# XboxSerialAdapter.net
KiCad netlist of a schematic drawn in EAGLE
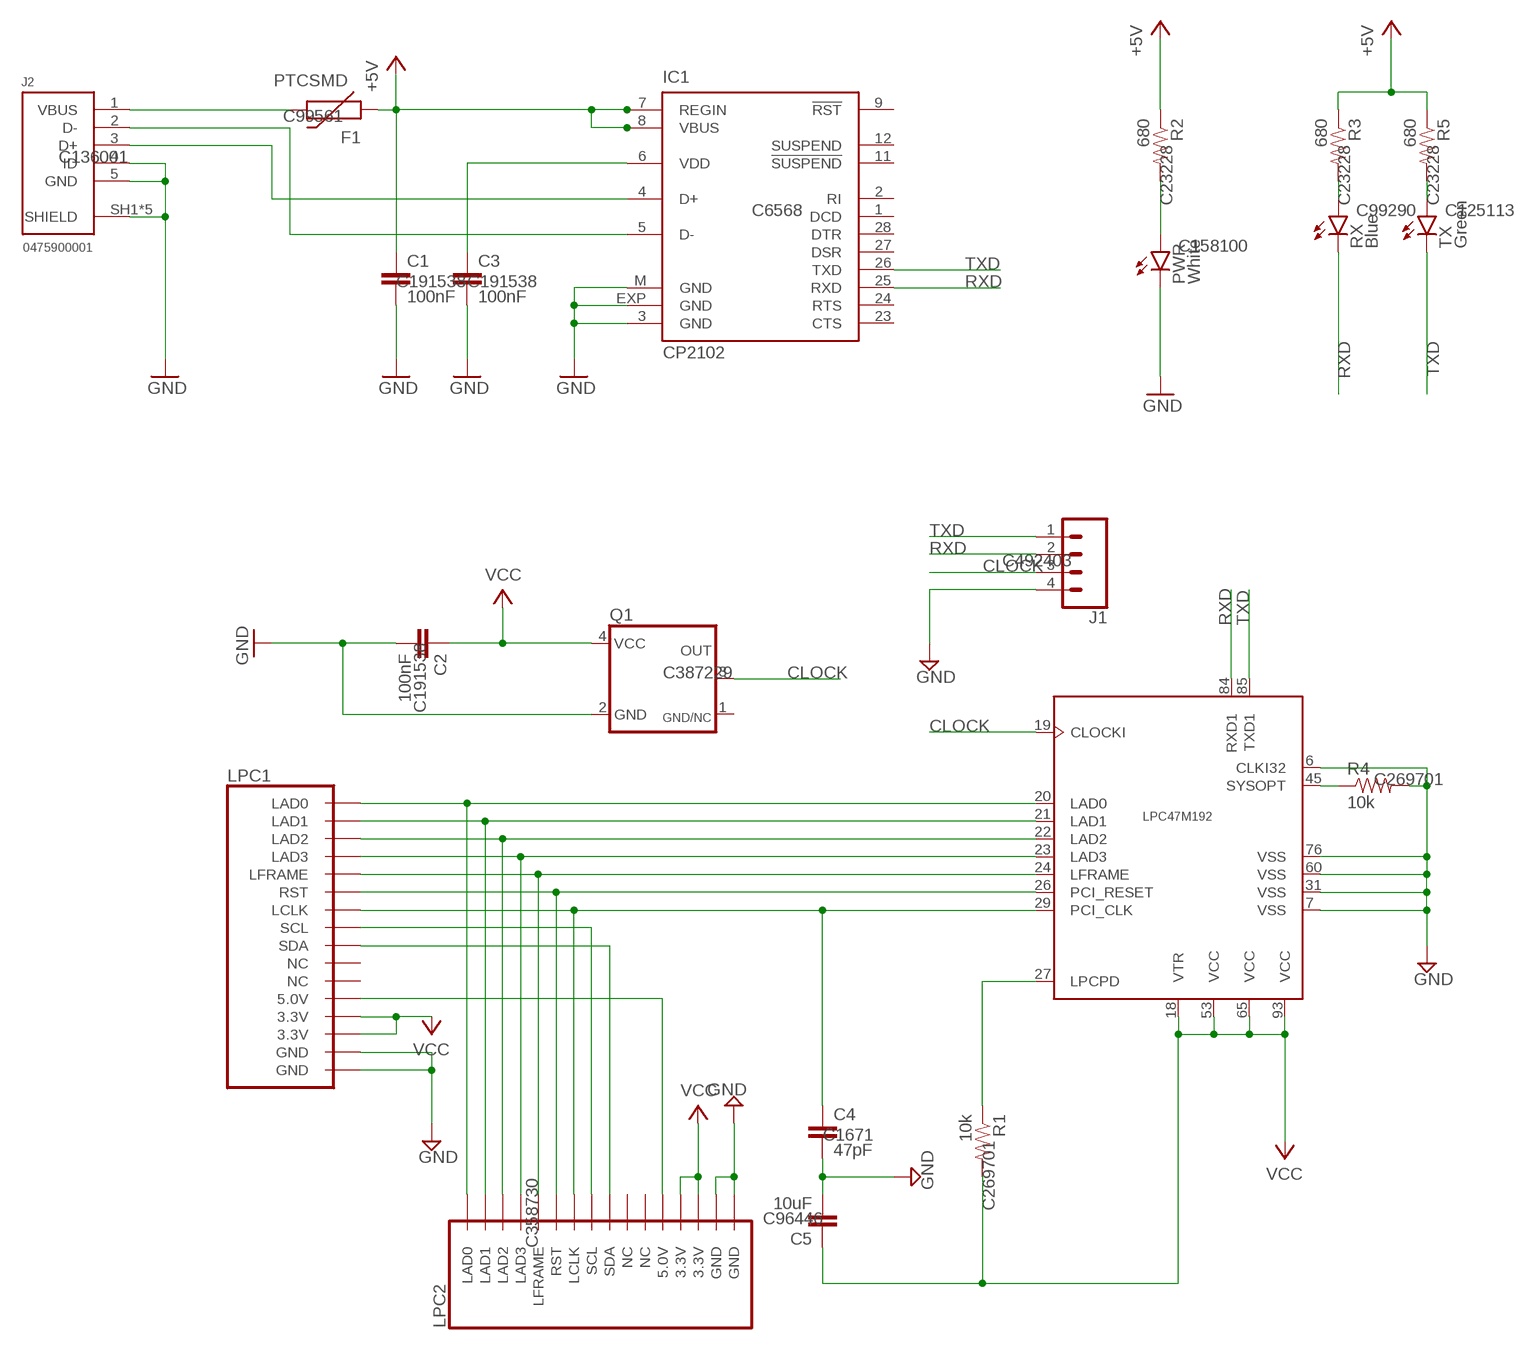
[diagram p0: schematic, sheet 1]

(export (version "E")
  (design (tool "Eeschema 10.0.6"))
  (components
    (comp (ref "C1")
      (value "100nF")
      (footprint "eagle-import:0603-CAP")
      (fields (field (name "LCSC_PART") "C191538"))
      (libsource (lib "eagle-import") (part "CAP0603-CAP"))
    )
    (comp (ref "C2")
      (value "100nF")
      (footprint "eagle-import:0603-CAP")
      (fields (field (name "LCSC_PART") "C191538"))
      (libsource (lib "eagle-import") (part "CAP0603-CAP"))
    )
    (comp (ref "C3")
      (value "100nF")
      (footprint "eagle-import:0603-CAP")
      (fields (field (name "LCSC_PART") "C191538"))
      (libsource (lib "eagle-import") (part "CAP0603-CAP"))
    )
    (comp (ref "C4")
      (value "47pF")
      (footprint "eagle-import:0603-CAP")
      (fields (field (name "LCSC_PART") "C1671"))
      (libsource (lib "eagle-import") (part "CAP0603-CAP"))
    )
    (comp (ref "C5")
      (value "10uF")
      (footprint "eagle-import:0603-CAP")
      (fields (field (name "LCSC_PART") "C96446"))
      (libsource (lib "eagle-import") (part "CAP0603-CAP"))
    )
    (comp (ref "F1")
      (value "PTCSMD")
      (footprint "eagle-import:PTC-1206")
      (fields (field (name "LCSC_PART") "C99561"))
      (libsource (lib "eagle-import") (part "PTCSMD"))
    )
    (comp (ref "IC1")
      (value "CP2102")
      (footprint "eagle-import:MLP28")
      (fields
        (field (name "MF") "FARNELL")
        (field (name "MPN") "CP2102-GM")
        (field (name "LCSC_PART") "C6568")
      )
      (libsource (lib "eagle-import") (part "CP2102"))
    )
    (comp (ref "J1")
      (value "CONN_04")
      (footprint "eagle-import:1X04")
      (fields (field (name "LCSC_PART") "C492403"))
      (libsource (lib "eagle-import") (part "CONN_04"))
    )
    (comp (ref "J2")
      (value "0475900001")
      (footprint "eagle-import:0475900001")
      (fields
        (field (name "DIGIKEY_PARTNO") "WM17144TR-ND")
        (field (name "MANUFACTURER") "Molex")
        (field (name "LCSC_PART") "C136001")
        (field (name "CREATED_BY") "PCBLayout.com")
      )
      (libsource (lib "eagle-import") (part "0475900001"))
    )
    (comp (ref "LPC1")
      (value "LPC_HEADERLPC_FEMALE")
      (footprint "eagle-import:HDRVR16W64P254_2X8_1524X508X254B")
      (fields (field (name "LCSC_PART") "C492425"))
      (libsource (lib "eagle-import") (part "LPC_HEADERLPC_FEMALE"))
    )
    (comp (ref "LPC2")
      (value "LPC_HEADERLPC_FEMALE")
      (footprint "eagle-import:HDRVR16W64P254_2X8_1524X508X254B")
      (fields (field (name "LCSC_PART") "C358730"))
      (libsource (lib "eagle-import") (part "LPC_HEADERLPC_FEMALE"))
    )
    (comp (ref "PWR")
      (value "White")
      (footprint "eagle-import:CHIP-LED0603")
      (fields (field (name "LCSC_PART") "C158100"))
      (libsource (lib "eagle-import") (part "LEDCHIP-LED0603"))
    )
    (comp (ref "Q1")
      (value "SCTF_C3872291")
      (footprint "eagle-import:SCTF_C387229")
      (fields (field (name "LCSC_PART") "C387229"))
      (libsource (lib "eagle-import") (part "SCTF_C3872291"))
    )
    (comp (ref "R1")
      (value "10k")
      (footprint "eagle-import:0603-RES")
      (fields (field (name "LCSC_PART") "C269701"))
      (libsource (lib "eagle-import") (part "RESISTOR0603-RES"))
    )
    (comp (ref "R2")
      (value "680")
      (footprint "eagle-import:0603-RES")
      (fields (field (name "LCSC_PART") "C23228"))
      (libsource (lib "eagle-import") (part "RESISTOR0603-RES"))
    )
    (comp (ref "R3")
      (value "680")
      (footprint "eagle-import:0603-RES")
      (fields (field (name "LCSC_PART") "C23228"))
      (libsource (lib "eagle-import") (part "RESISTOR0603-RES"))
    )
    (comp (ref "R4")
      (value "10k")
      (footprint "eagle-import:0603-RES")
      (fields (field (name "LCSC_PART") "C269701"))
      (libsource (lib "eagle-import") (part "RESISTOR0603-RES"))
    )
    (comp (ref "R5")
      (value "680")
      (footprint "eagle-import:0603-RES")
      (fields (field (name "LCSC_PART") "C23228"))
      (libsource (lib "eagle-import") (part "RESISTOR0603-RES"))
    )
    (comp (ref "RX")
      (value "Blue")
      (footprint "eagle-import:CHIP-LED0603")
      (fields (field (name "LCSC_PART") "C99290"))
      (libsource (lib "eagle-import") (part "LEDCHIP-LED0603"))
    )
    (comp (ref "TX")
      (value "Green")
      (footprint "eagle-import:CHIP-LED0603")
      (fields (field (name "LCSC_PART") "C125113"))
      (libsource (lib "eagle-import") (part "LEDCHIP-LED0603"))
    )
    (comp (ref "U1")
      (value "LPC47M192")
      (footprint "eagle-import:QFP128")
      (libsource (lib "eagle-import") (part "LPC47M192"))
    )
  )
  (nets
    (net (code "1") (name "+5V") (class "Default")
      (node (ref "C1") (pin "1") (pinfunction "1_1") (pintype "passive"))
      (node (ref "F1") (pin "1") (pinfunction "1_1") (pintype "bidirectional"))
      (node (ref "IC1") (pin "7") (pinfunction "REGIN_7") (pintype "passive"))
      (node (ref "IC1") (pin "8") (pinfunction "VBUS_8") (pintype "input"))
      (node (ref "R2") (pin "1") (pinfunction "1_1") (pintype "passive"))
      (node (ref "R3") (pin "1") (pinfunction "1_1") (pintype "passive"))
      (node (ref "R5") (pin "1") (pinfunction "1_1") (pintype "passive"))
    )
    (net (code "2") (name "/CLOCK") (class "Default")
      (node (ref "J1") (pin "3") (pinfunction "3_3") (pintype "passive"))
      (node (ref "Q1") (pin "3") (pinfunction "OUT_3") (pintype "output"))
      (node (ref "U1") (pin "19") (pinfunction "CLOCKI_19") (pintype "input"))
    )
    (net (code "3") (name "/GND{slash}NC") (class "Default")
      (node (ref "Q1") (pin "1") (pinfunction "GND/NC_1") (pintype "power_in"))
    )
    (net (code "4") (name "/RXD") (class "Default")
      (node (ref "IC1") (pin "25") (pinfunction "RXD_25") (pintype "input"))
      (node (ref "J1") (pin "2") (pinfunction "2_2") (pintype "passive"))
      (node (ref "RX") (pin "C") (pinfunction "C_C") (pintype "passive"))
      (node (ref "U1") (pin "84") (pinfunction "RXD1_84") (pintype "input"))
    )
    (net (code "5") (name "/TXD") (class "Default")
      (node (ref "IC1") (pin "26") (pinfunction "TXD_26") (pintype "output"))
      (node (ref "J1") (pin "1") (pinfunction "1_1") (pintype "passive"))
      (node (ref "TX") (pin "C") (pinfunction "C_C") (pintype "passive"))
      (node (ref "U1") (pin "85") (pinfunction "TXD1_85") (pintype "output"))
    )
    (net (code "6") (name "GND") (class "Default")
      (node (ref "C1") (pin "2") (pinfunction "2_2") (pintype "passive"))
      (node (ref "C2") (pin "2") (pinfunction "2_2") (pintype "passive"))
      (node (ref "C3") (pin "2") (pinfunction "2_2") (pintype "passive"))
      (node (ref "C4") (pin "2") (pinfunction "2_2") (pintype "passive"))
      (node (ref "C5") (pin "2") (pinfunction "2_2") (pintype "passive"))
      (node (ref "IC1") (pin "3") (pinfunction "GND_3") (pintype "power_in"))
      (node (ref "IC1") (pin "EXP") (pinfunction "GND_EXP") (pintype "power_in"))
      (node (ref "IC1") (pin "M") (pinfunction "GND_M") (pintype "power_in"))
      (node (ref "J1") (pin "4") (pinfunction "4_4") (pintype "passive"))
      (node (ref "J2") (pin "4") (pinfunction "ID_4") (pintype "passive"))
      (node (ref "J2") (pin "5") (pinfunction "GND_5") (pintype "passive"))
      (node (ref "J2") (pin "SH1") (pinfunction "SHIELD_SH1") (pintype "power_in"))
      (node (ref "J2") (pin "SH2") (pinfunction "SHIELD_SH2") (pintype "power_in"))
      (node (ref "J2") (pin "SH3") (pinfunction "SHIELD_SH3") (pintype "power_in"))
      (node (ref "J2") (pin "SH4") (pinfunction "SHIELD_SH4") (pintype "power_in"))
      (node (ref "J2") (pin "SH5") (pinfunction "SHIELD_SH5") (pintype "power_in"))
      (node (ref "LPC1") (pin "12") (pinfunction "GND_12") (pintype "power_in"))
      (node (ref "LPC1") (pin "2") (pinfunction "GND_2") (pintype "power_in"))
      (node (ref "LPC2") (pin "12") (pinfunction "GND_12") (pintype "power_in"))
      (node (ref "LPC2") (pin "2") (pinfunction "GND_2") (pintype "power_in"))
      (node (ref "PWR") (pin "C") (pinfunction "C_C") (pintype "passive"))
      (node (ref "Q1") (pin "2") (pinfunction "GND_2") (pintype "power_in"))
      (node (ref "R4") (pin "2") (pinfunction "2_2") (pintype "passive"))
      (node (ref "U1") (pin "31") (pinfunction "VSS_31") (pintype "power_in"))
      (node (ref "U1") (pin "6") (pinfunction "CLKI32_6") (pintype "input"))
      (node (ref "U1") (pin "60") (pinfunction "VSS_60") (pintype "power_in"))
      (node (ref "U1") (pin "7") (pinfunction "VSS_7") (pintype "power_in"))
      (node (ref "U1") (pin "76") (pinfunction "VSS_76") (pintype "power_in"))
    )
    (net (code "7") (name "Net-(IC1-D+)") (class "Default")
      (node (ref "IC1") (pin "4") (pinfunction "D+_4") (pintype "bidirectional"))
      (node (ref "J2") (pin "3") (pinfunction "D+_3") (pintype "passive"))
    )
    (net (code "8") (name "Net-(IC1-D-)") (class "Default")
      (node (ref "IC1") (pin "5") (pinfunction "D-_5") (pintype "bidirectional"))
      (node (ref "J2") (pin "2") (pinfunction "D-_2") (pintype "passive"))
    )
    (net (code "9") (name "Net-(IC1-VDD)") (class "Default")
      (node (ref "C3") (pin "1") (pinfunction "1_1") (pintype "passive"))
      (node (ref "IC1") (pin "6") (pinfunction "VDD_6") (pintype "power_in"))
    )
    (net (code "10") (name "Net-(J2-VBUS)") (class "Default")
      (node (ref "F1") (pin "2") (pinfunction "2_2") (pintype "bidirectional"))
      (node (ref "J2") (pin "1") (pinfunction "VBUS_1") (pintype "passive"))
    )
    (net (code "11") (name "Net-(LPC1-5.0V)") (class "Default")
      (node (ref "LPC1") (pin "6") (pinfunction "5.0V_6") (pintype "power_in"))
      (node (ref "LPC2") (pin "6") (pinfunction "5.0V_6") (pintype "power_in"))
    )
    (net (code "12") (name "Net-(LPC1-LAD0)") (class "Default")
      (node (ref "LPC1") (pin "11") (pinfunction "LAD0_11") (pintype "passive"))
      (node (ref "LPC2") (pin "11") (pinfunction "LAD0_11") (pintype "passive"))
      (node (ref "U1") (pin "20") (pinfunction "LAD0_20") (pintype "bidirectional"))
    )
    (net (code "13") (name "Net-(LPC1-LAD1)") (class "Default")
      (node (ref "LPC1") (pin "10") (pinfunction "LAD1_10") (pintype "passive"))
      (node (ref "LPC2") (pin "10") (pinfunction "LAD1_10") (pintype "passive"))
      (node (ref "U1") (pin "21") (pinfunction "LAD1_21") (pintype "bidirectional"))
    )
    (net (code "14") (name "Net-(LPC1-LAD2)") (class "Default")
      (node (ref "LPC1") (pin "8") (pinfunction "LAD2_8") (pintype "passive"))
      (node (ref "LPC2") (pin "8") (pinfunction "LAD2_8") (pintype "passive"))
      (node (ref "U1") (pin "22") (pinfunction "LAD2_22") (pintype "bidirectional"))
    )
    (net (code "15") (name "Net-(LPC1-LAD3)") (class "Default")
      (node (ref "LPC1") (pin "7") (pinfunction "LAD3_7") (pintype "passive"))
      (node (ref "LPC2") (pin "7") (pinfunction "LAD3_7") (pintype "passive"))
      (node (ref "U1") (pin "23") (pinfunction "LAD3_23") (pintype "bidirectional"))
    )
    (net (code "16") (name "Net-(LPC1-LCLK)") (class "Default")
      (node (ref "C4") (pin "1") (pinfunction "1_1") (pintype "passive"))
      (node (ref "LPC1") (pin "1") (pinfunction "LCLK_1") (pintype "passive"))
      (node (ref "LPC2") (pin "1") (pinfunction "LCLK_1") (pintype "passive"))
      (node (ref "U1") (pin "29") (pinfunction "PCI_CLK_29") (pintype "input"))
    )
    (net (code "17") (name "Net-(LPC1-LFRAME)") (class "Default")
      (node (ref "LPC1") (pin "3") (pinfunction "LFRAME_3") (pintype "passive"))
      (node (ref "LPC2") (pin "3") (pinfunction "LFRAME_3") (pintype "passive"))
      (node (ref "U1") (pin "24") (pinfunction "LFRAME_24") (pintype "input"))
    )
    (net (code "18") (name "Net-(LPC1-RST)") (class "Default")
      (node (ref "LPC1") (pin "5") (pinfunction "RST_5") (pintype "passive"))
      (node (ref "LPC2") (pin "5") (pinfunction "RST_5") (pintype "passive"))
      (node (ref "U1") (pin "26") (pinfunction "PCI_RESET_26") (pintype "input"))
    )
    (net (code "19") (name "Net-(LPC1-SCL)") (class "Default")
      (node (ref "LPC1") (pin "13") (pinfunction "SCL_13") (pintype "passive"))
      (node (ref "LPC2") (pin "13") (pinfunction "SCL_13") (pintype "passive"))
    )
    (net (code "20") (name "Net-(LPC1-SDA)") (class "Default")
      (node (ref "LPC1") (pin "14") (pinfunction "SDA_14") (pintype "passive"))
      (node (ref "LPC2") (pin "14") (pinfunction "SDA_14") (pintype "passive"))
    )
    (net (code "21") (name "Net-(PWR-PadA)") (class "Default")
      (node (ref "PWR") (pin "A") (pinfunction "A_A") (pintype "passive"))
      (node (ref "R2") (pin "2") (pinfunction "2_2") (pintype "passive"))
    )
    (net (code "22") (name "Net-(R3-Pad2)") (class "Default")
      (node (ref "R3") (pin "2") (pinfunction "2_2") (pintype "passive"))
      (node (ref "RX") (pin "A") (pinfunction "A_A") (pintype "passive"))
    )
    (net (code "23") (name "Net-(R5-Pad2)") (class "Default")
      (node (ref "R5") (pin "2") (pinfunction "2_2") (pintype "passive"))
      (node (ref "TX") (pin "A") (pinfunction "A_A") (pintype "passive"))
    )
    (net (code "24") (name "Net-(U1-LPCPD)") (class "Default")
      (node (ref "R1") (pin "1") (pinfunction "1_1") (pintype "passive"))
      (node (ref "U1") (pin "27") (pinfunction "LPCPD_27") (pintype "input"))
    )
    (net (code "25") (name "Net-(U1-SYSOPT)") (class "Default")
      (node (ref "R4") (pin "1") (pinfunction "1_1") (pintype "passive"))
      (node (ref "U1") (pin "45") (pinfunction "SYSOPT_45") (pintype "bidirectional"))
    )
    (net (code "26") (name "VCC") (class "Default")
      (node (ref "C2") (pin "1") (pinfunction "1_1") (pintype "passive"))
      (node (ref "C5") (pin "1") (pinfunction "1_1") (pintype "passive"))
      (node (ref "LPC1") (pin "15") (pinfunction "3.3V_15") (pintype "power_in"))
      (node (ref "LPC1") (pin "9") (pinfunction "3.3V_9") (pintype "power_in"))
      (node (ref "LPC2") (pin "15") (pinfunction "3.3V_15") (pintype "power_in"))
      (node (ref "LPC2") (pin "9") (pinfunction "3.3V_9") (pintype "power_in"))
      (node (ref "Q1") (pin "4") (pinfunction "VCC_4") (pintype "power_in"))
      (node (ref "R1") (pin "2") (pinfunction "2_2") (pintype "passive"))
      (node (ref "U1") (pin "18") (pinfunction "VTR_18") (pintype "power_in"))
      (node (ref "U1") (pin "53") (pinfunction "VCC_53") (pintype "power_in"))
      (node (ref "U1") (pin "65") (pinfunction "VCC_65") (pintype "power_in"))
      (node (ref "U1") (pin "93") (pinfunction "VCC_93") (pintype "power_in"))
    )
    (net (code "27") (name "unconnected-(IC1-CTS-Pad23)") (class "Default")
      (node (ref "IC1") (pin "23") (pinfunction "CTS_23") (pintype "input"))
    )
    (net (code "28") (name "unconnected-(IC1-DCD-Pad1)") (class "Default")
      (node (ref "IC1") (pin "1") (pinfunction "DCD_1") (pintype "input"))
    )
    (net (code "29") (name "unconnected-(IC1-DSR-Pad27)") (class "Default")
      (node (ref "IC1") (pin "27") (pinfunction "DSR_27") (pintype "input"))
    )
    (net (code "30") (name "unconnected-(IC1-DTR-Pad28)") (class "Default")
      (node (ref "IC1") (pin "28") (pinfunction "DTR_28") (pintype "output"))
    )
    (net (code "31") (name "unconnected-(IC1-RI-Pad2)") (class "Default")
      (node (ref "IC1") (pin "2") (pinfunction "RI_2") (pintype "input"))
    )
    (net (code "32") (name "unconnected-(IC1-RTS-Pad24)") (class "Default")
      (node (ref "IC1") (pin "24") (pinfunction "RTS_24") (pintype "output"))
    )
    (net (code "33") (name "unconnected-(IC1-SUSPEND-Pad12)") (class "Default")
      (node (ref "IC1") (pin "12") (pinfunction "SUSPEND_12") (pintype "output"))
    )
    (net (code "34") (name "unconnected-(IC1-~{RST}-Pad9)") (class "Default")
      (node (ref "IC1") (pin "9") (pinfunction "~{RST}_9") (pintype "bidirectional"))
    )
    (net (code "35") (name "unconnected-(IC1-~{SUSPEND}-Pad11)") (class "Default")
      (node (ref "IC1") (pin "11") (pinfunction "~{SUSPEND}_11") (pintype "output"))
    )
    (net (code "36") (name "unconnected-(LPC1-NC-Pad4)") (class "Default")
      (node (ref "LPC1") (pin "4") (pinfunction "NC_4") (pintype "no_connect"))
    )
    (net (code "37") (name "unconnected-(LPC1-NC-Pad16)") (class "Default")
      (node (ref "LPC1") (pin "16") (pinfunction "NC_16") (pintype "no_connect"))
    )
    (net (code "38") (name "unconnected-(LPC2-NC-Pad4)") (class "Default")
      (node (ref "LPC2") (pin "4") (pinfunction "NC_4") (pintype "no_connect"))
    )
    (net (code "39") (name "unconnected-(LPC2-NC-Pad16)") (class "Default")
      (node (ref "LPC2") (pin "16") (pinfunction "NC_16") (pintype "no_connect"))
    )
  )
)
